# driver.net
KiCad netlist of a schematic drawn in EAGLE
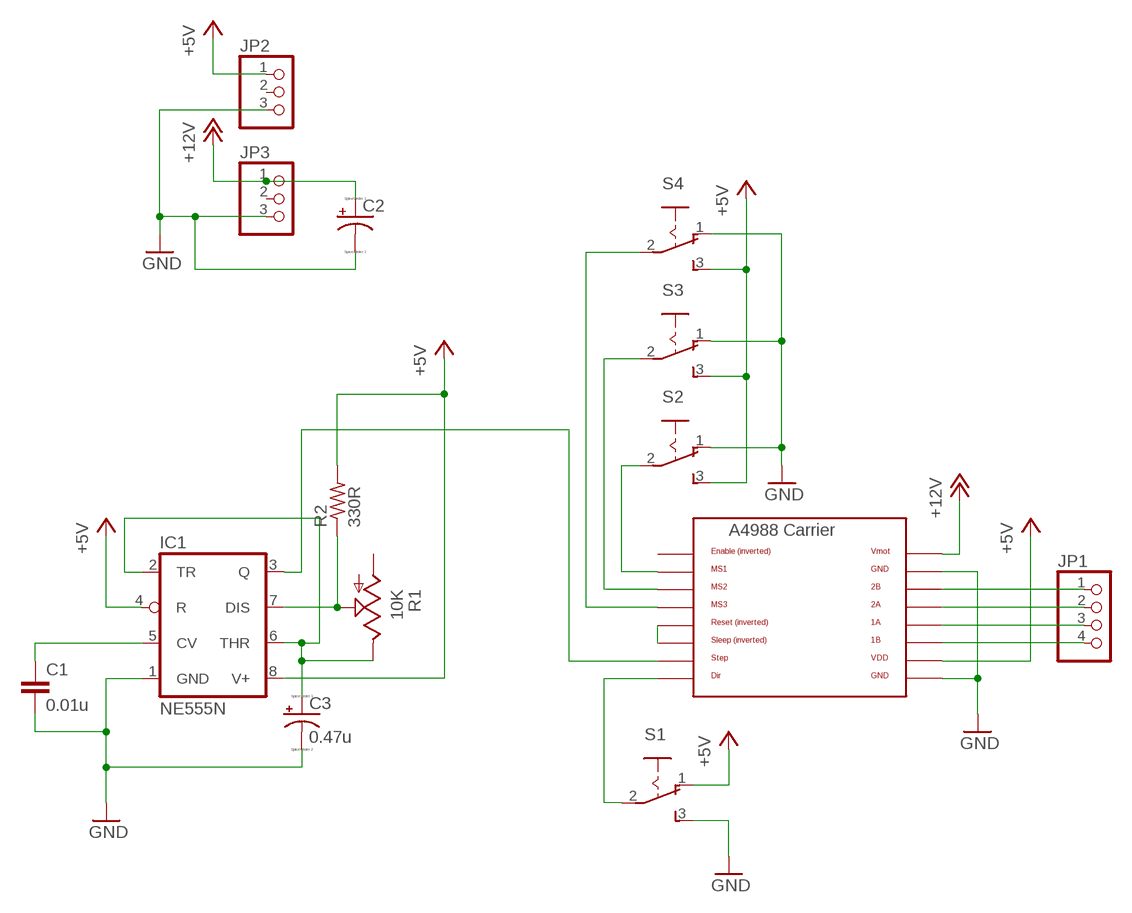
[diagram p0: schematic, sheet 1]

(export (version "E")
  (design (tool "Eeschema 10.0.6"))
  (components
    (comp (ref "C1")
      (value "0.01u")
      (footprint "eagle-import:C0603")
      (libsource (lib "eagle-import") (part "C-EUC0603"))
    )
    (comp (ref "C2")
      (value "CPOL-USE5-6")
      (footprint "eagle-import:E5-6")
      (libsource (lib "eagle-import") (part "CPOL-USE5-6"))
    )
    (comp (ref "C3")
      (value "0.47u")
      (footprint "eagle-import:E2,5-6E")
      (libsource (lib "eagle-import") (part "CPOL-USE2,5-6E"))
    )
    (comp (ref "IC1")
      (value "NE555N")
      (footprint "eagle-import:DIL08")
      (libsource (lib "eagle-import") (part "555NNE"))
    )
    (comp (ref "JP1")
      (value "PINHD-1X4/90")
      (footprint "eagle-import:1X04_90")
      (libsource (lib "eagle-import") (part "PINHD-1X4/90"))
    )
    (comp (ref "JP2")
      (value "PINHD-1X3")
      (footprint "eagle-import:1X03")
      (libsource (lib "eagle-import") (part "PINHD-1X3"))
    )
    (comp (ref "JP3")
      (value "PINHD-1X3")
      (footprint "eagle-import:1X03")
      (libsource (lib "eagle-import") (part "PINHD-1X3"))
    )
    (comp (ref "R1")
      (value "10K")
      (footprint "eagle-import:RJ9W")
      (libsource (lib "eagle-import") (part "TRIM_US-RJ9W"))
    )
    (comp (ref "R2")
      (value "330R")
      (footprint "eagle-import:R0603")
      (libsource (lib "eagle-import") (part "R-US_R0603"))
    )
    (comp (ref "S1")
      (value "M251")
      (footprint "eagle-import:M251")
      (libsource (lib "eagle-import") (part "M251"))
    )
    (comp (ref "S2")
      (value "M251")
      (footprint "eagle-import:M251")
      (libsource (lib "eagle-import") (part "M251"))
    )
    (comp (ref "S3")
      (value "M251")
      (footprint "eagle-import:M251")
      (libsource (lib "eagle-import") (part "M251"))
    )
    (comp (ref "S4")
      (value "M251")
      (footprint "eagle-import:M251")
      (libsource (lib "eagle-import") (part "M251"))
    )
    (comp (ref "U$1")
      (value "A4988BREAKOUT")
      (footprint "eagle-import:A4988BREAKOUT")
      (libsource (lib "eagle-import") (part "A4988BREAKOUT"))
    )
  )
  (nets
    (net (code "1") (name "+5V") (class "Default")
      (node (ref "IC1") (pin "4") (pinfunction "R_4") (pintype "input"))
      (node (ref "IC1") (pin "8") (pinfunction "V+_8") (pintype "power_in"))
      (node (ref "JP2") (pin "1") (pinfunction "1_1") (pintype "passive"))
      (node (ref "R2") (pin "2") (pinfunction "2_2") (pintype "passive"))
      (node (ref "S1") (pin "1") (pinfunction "O_1") (pintype "passive"))
      (node (ref "S2") (pin "3") (pinfunction "S_3") (pintype "passive"))
      (node (ref "S3") (pin "3") (pinfunction "S_3") (pintype "passive"))
      (node (ref "S4") (pin "3") (pinfunction "S_3") (pintype "passive"))
      (node (ref "U$1") (pin "VDD") (pinfunction "VDD_VDD") (pintype "power_in"))
    )
    (net (code "2") (name "+12V") (class "Default")
      (node (ref "C2") (pin "+") (pinfunction "+_+") (pintype "passive"))
      (node (ref "JP3") (pin "1") (pinfunction "1_1") (pintype "passive"))
      (node (ref "U$1") (pin "VMOT") (pinfunction "VMOT_VMOT") (pintype "power_in"))
    )
    (net (code "3") (name "GND") (class "Default")
      (node (ref "C1") (pin "2") (pinfunction "2_2") (pintype "passive"))
      (node (ref "C2") (pin "-") (pinfunction "-_-") (pintype "passive"))
      (node (ref "C3") (pin "-") (pinfunction "-_-") (pintype "passive"))
      (node (ref "IC1") (pin "1") (pinfunction "GND_1") (pintype "power_in"))
      (node (ref "JP2") (pin "3") (pinfunction "3_3") (pintype "passive"))
      (node (ref "JP3") (pin "3") (pinfunction "3_3") (pintype "passive"))
      (node (ref "S1") (pin "3") (pinfunction "S_3") (pintype "passive"))
      (node (ref "S2") (pin "1") (pinfunction "O_1") (pintype "passive"))
      (node (ref "S3") (pin "1") (pinfunction "O_1") (pintype "passive"))
      (node (ref "S4") (pin "1") (pinfunction "O_1") (pintype "passive"))
      (node (ref "U$1") (pin "GND") (pinfunction "GND_GND") (pintype "power_in"))
      (node (ref "U$1") (pin "GND@0") (pinfunction "GND_GND@0") (pintype "power_in"))
    )
    (net (code "4") (name "Net-(IC1-CV)") (class "Default")
      (node (ref "C1") (pin "1") (pinfunction "1_1") (pintype "passive"))
      (node (ref "IC1") (pin "5") (pinfunction "CV_5") (pintype "input"))
    )
    (net (code "5") (name "Net-(IC1-DIS)") (class "Default")
      (node (ref "IC1") (pin "7") (pinfunction "DIS_7") (pintype "input"))
      (node (ref "R1") (pin "S") (pinfunction "S_S") (pintype "passive"))
      (node (ref "R2") (pin "1") (pinfunction "1_1") (pintype "passive"))
    )
    (net (code "6") (name "Net-(IC1-Q)") (class "Default")
      (node (ref "IC1") (pin "3") (pinfunction "Q_3") (pintype "output"))
      (node (ref "U$1") (pin "STEP") (pinfunction "STEP_STEP") (pintype "input"))
    )
    (net (code "7") (name "Net-(IC1-THR)") (class "Default")
      (node (ref "C3") (pin "+") (pinfunction "+_+") (pintype "passive"))
      (node (ref "IC1") (pin "2") (pinfunction "TR_2") (pintype "input"))
      (node (ref "IC1") (pin "6") (pinfunction "THR_6") (pintype "input"))
      (node (ref "R1") (pin "E") (pinfunction "E_E") (pintype "passive"))
    )
    (net (code "8") (name "Net-(JP1-Pad1)") (class "Default")
      (node (ref "JP1") (pin "1") (pinfunction "1_1") (pintype "passive"))
      (node (ref "U$1") (pin "2B") (pinfunction "2B_2B") (pintype "output"))
    )
    (net (code "9") (name "Net-(JP1-Pad2)") (class "Default")
      (node (ref "JP1") (pin "2") (pinfunction "2_2") (pintype "passive"))
      (node (ref "U$1") (pin "2A") (pinfunction "2A_2A") (pintype "output"))
    )
    (net (code "10") (name "Net-(JP1-Pad3)") (class "Default")
      (node (ref "JP1") (pin "3") (pinfunction "3_3") (pintype "passive"))
      (node (ref "U$1") (pin "1A") (pinfunction "1A_1A") (pintype "output"))
    )
    (net (code "11") (name "Net-(JP1-Pad4)") (class "Default")
      (node (ref "JP1") (pin "4") (pinfunction "4_4") (pintype "passive"))
      (node (ref "U$1") (pin "1B") (pinfunction "1B_1B") (pintype "output"))
    )
    (net (code "12") (name "Net-(S1-P)") (class "Default")
      (node (ref "S1") (pin "2") (pinfunction "P_2") (pintype "passive"))
      (node (ref "U$1") (pin "DIR") (pinfunction "DIR_DIR") (pintype "input"))
    )
    (net (code "13") (name "Net-(S2-P)") (class "Default")
      (node (ref "S2") (pin "2") (pinfunction "P_2") (pintype "passive"))
      (node (ref "U$1") (pin "MS1") (pinfunction "MS1_MS1") (pintype "input"))
    )
    (net (code "14") (name "Net-(S3-P)") (class "Default")
      (node (ref "S3") (pin "2") (pinfunction "P_2") (pintype "passive"))
      (node (ref "U$1") (pin "MS2") (pinfunction "MS2_MS2") (pintype "input"))
    )
    (net (code "15") (name "Net-(S4-P)") (class "Default")
      (node (ref "S4") (pin "2") (pinfunction "P_2") (pintype "passive"))
      (node (ref "U$1") (pin "MS3") (pinfunction "MS3_MS3") (pintype "input"))
    )
    (net (code "16") (name "Net-(U$1-SLEEP)") (class "Default")
      (node (ref "U$1") (pin "RST") (pinfunction "RST_RST") (pintype "input"))
      (node (ref "U$1") (pin "SLP") (pinfunction "SLEEP_SLP") (pintype "input"))
    )
    (net (code "17") (name "unconnected-(JP2-Pad2)") (class "Default")
      (node (ref "JP2") (pin "2") (pinfunction "2_2") (pintype "passive"))
    )
    (net (code "18") (name "unconnected-(JP3-Pad2)") (class "Default")
      (node (ref "JP3") (pin "2") (pinfunction "2_2") (pintype "passive"))
    )
    (net (code "19") (name "unconnected-(R1-PadA)") (class "Default")
      (node (ref "R1") (pin "A") (pinfunction "A_A") (pintype "passive"))
    )
    (net (code "20") (name "unconnected-(U$1-PadEN)") (class "Default")
      (node (ref "U$1") (pin "EN") (pinfunction "EN_EN") (pintype "input"))
    )
  )
)
